# Punto2.net
KiCad netlist of a schematic drawn in Altium Designer
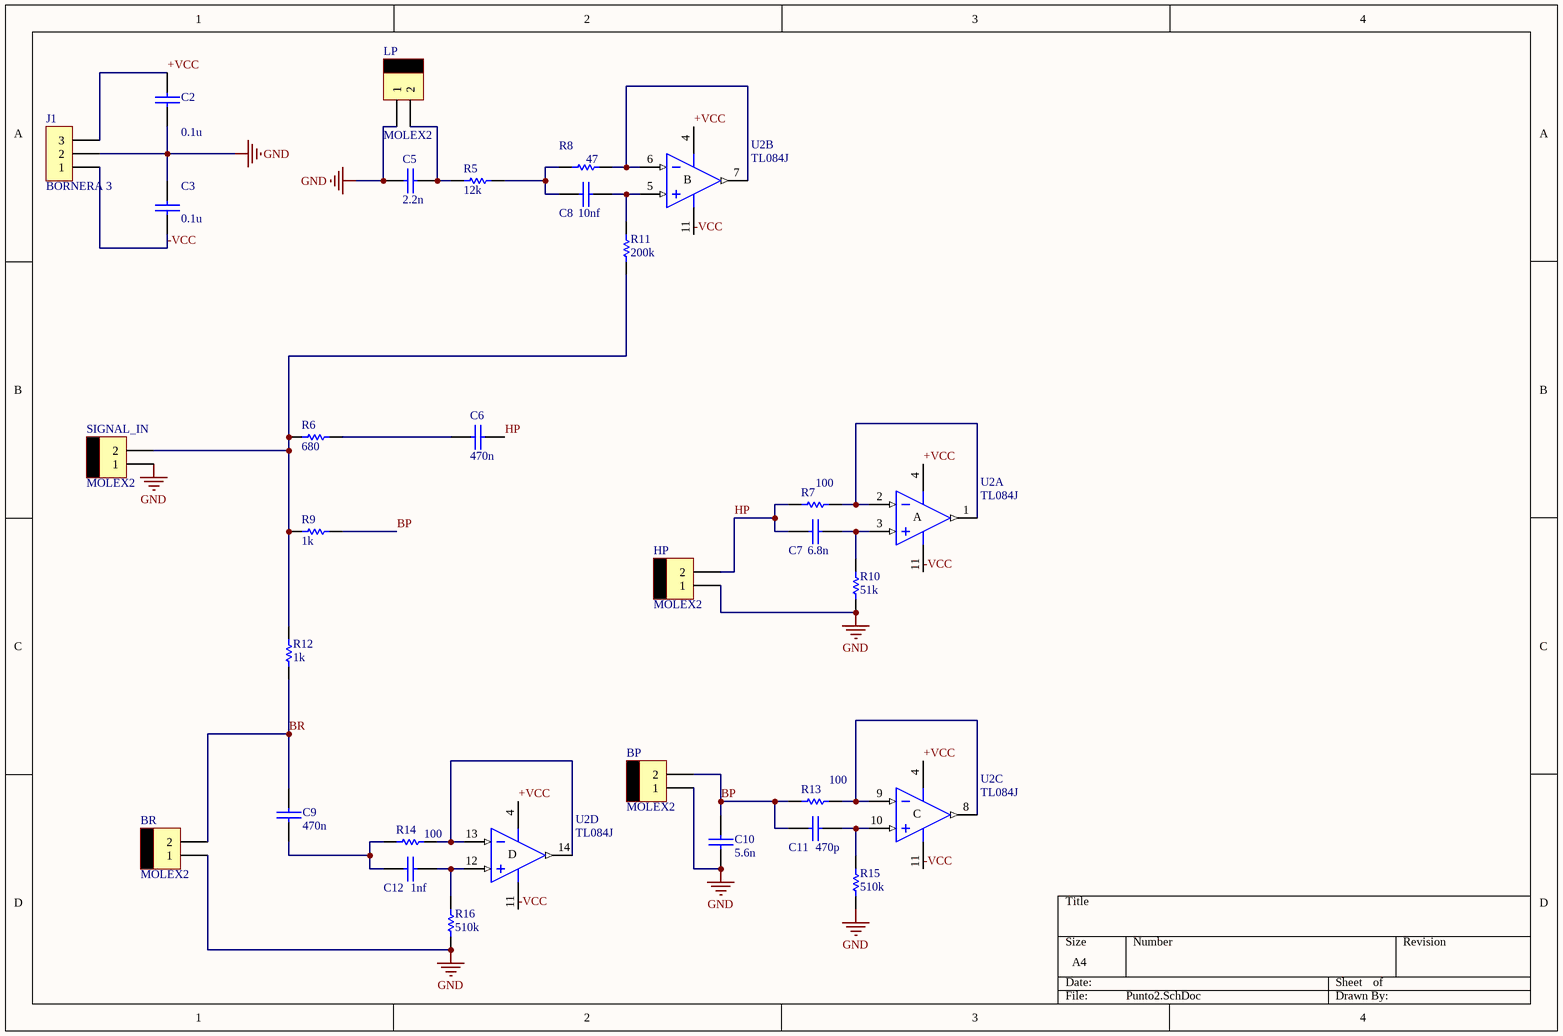
[diagram p0: Punto2.SchDoc]

(export (version "E")
  (design (tool "Eeschema 10.0.6"))
  (components
    (comp (ref "BP") (value "MOLEX2") (footprint "MOLEX2") (libsource (lib "LIBEBAL") (part "MOLEX2")))
    (comp (ref "BR") (value "MOLEX2") (footprint "MOLEX2") (libsource (lib "LIBEBAL") (part "MOLEX2")))
    (comp (ref "C2") (value "0.1u") (footprint "CAP200") (libsource (lib "LIBEBAL") (part "CAP")))
    (comp (ref "C3") (value "0.1u") (footprint "CAP200") (libsource (lib "LIBEBAL") (part "CAP")))
    (comp (ref "C5") (value "2.2n") (footprint "0805") (libsource (lib "LIBEBAL") (part "CAP")))
    (comp (ref "C6") (value "470n") (footprint "0805") (libsource (lib "LIBEBAL") (part "CAP")))
    (comp (ref "C7") (value "6.8n") (footprint "0805") (libsource (lib "LIBEBAL") (part "CAP")))
    (comp (ref "C8") (value "10nf") (footprint "0805") (libsource (lib "LIBEBAL") (part "CAP")))
    (comp (ref "C9") (value "470n") (footprint "0805") (libsource (lib "LIBEBAL") (part "CAP")))
    (comp (ref "C10") (value "5.6n") (footprint "0805") (libsource (lib "LIBEBAL") (part "CAP")))
    (comp (ref "C11") (value "470p") (footprint "0805") (libsource (lib "LIBEBAL") (part "CAP")))
    (comp (ref "C12") (value "1nf") (footprint "0805") (libsource (lib "LIBEBAL") (part "CAP")))
    (comp (ref "HP") (value "MOLEX2") (footprint "MOLEX2") (libsource (lib "LIBEBAL") (part "MOLEX2")))
    (comp (ref "J1")
      (value "BORNERA 3")
      (footprint "BORNERA3")
      (libsource (lib "LIBEBAL") (part "BORNERA 3"))
    )
    (comp (ref "LP") (value "MOLEX2") (footprint "MOLEX2") (libsource (lib "") (part "MOLEX2_1")))
    (comp (ref "R5") (value "12k") (footprint "0805") (libsource (lib "LIBEBAL") (part "RES")))
    (comp (ref "R6") (value "680") (footprint "0805") (libsource (lib "LIBEBAL") (part "RES")))
    (comp (ref "R7") (value "100") (footprint "0805") (libsource (lib "LIBEBAL") (part "RES")))
    (comp (ref "R8") (value "47") (footprint "0805") (libsource (lib "LIBEBAL") (part "RES")))
    (comp (ref "R9") (value "1k") (footprint "0805") (libsource (lib "LIBEBAL") (part "RES")))
    (comp (ref "R10") (value "51k") (footprint "0805") (libsource (lib "LIBEBAL") (part "RES")))
    (comp (ref "R11") (value "200k") (footprint "0805") (libsource (lib "LIBEBAL") (part "RES")))
    (comp (ref "R12") (value "1k") (footprint "0805") (libsource (lib "LIBEBAL") (part "RES")))
    (comp (ref "R13") (value "100") (footprint "0805") (libsource (lib "LIBEBAL") (part "RES")))
    (comp (ref "R14") (value "100") (footprint "0805") (libsource (lib "LIBEBAL") (part "RES")))
    (comp (ref "R15") (value "510k") (footprint "0805") (libsource (lib "LIBEBAL") (part "RES")))
    (comp (ref "R16") (value "510k") (footprint "0805") (libsource (lib "LIBEBAL") (part "RES")))
    (comp (ref "SIGNAL_IN") (value "MOLEX2") (footprint "MOLEX2") (libsource (lib "LIBEBAL") (part "MOLEX2")))
    (comp (ref "U2")
      (value "TL084J")
      (footprint "J014")
      (description "JFET-Input Operational Amplifier")
      (fields (field (name "PUBLISHER") "Altium Limited"))
      (libsource (lib "TI Operational Amplifier") (part "TL084J"))
    )
  )
  (nets
    (net (code "1") (name "/+VCC") (class "Default")
      (node (ref "C2") (pin "1") (pinfunction "1_1") (pintype "passive"))
      (node (ref "J1") (pin "3") (pinfunction "3_3") (pintype "passive"))
      (node (ref "U2") (pin "4") (pinfunction "V+_4") (pintype "power_in"))
    )
    (net (code "2") (name "/-VCC") (class "Default")
      (node (ref "C3") (pin "2") (pinfunction "2_2") (pintype "passive"))
      (node (ref "J1") (pin "1") (pinfunction "1_1") (pintype "passive"))
      (node (ref "U2") (pin "11") (pinfunction "V-_11") (pintype "power_in"))
    )
    (net (code "3") (name "/BP") (class "Default")
      (node (ref "BP") (pin "2") (pinfunction "2_2") (pintype "passive"))
      (node (ref "C10") (pin "1") (pinfunction "1_1") (pintype "passive"))
      (node (ref "C11") (pin "1") (pinfunction "1_1") (pintype "passive"))
      (node (ref "R13") (pin "1") (pinfunction "1_1") (pintype "passive"))
      (node (ref "R9") (pin "2") (pinfunction "2_2") (pintype "passive"))
    )
    (net (code "4") (name "/BR") (class "Default")
      (node (ref "BR") (pin "2") (pinfunction "2_2") (pintype "passive"))
      (node (ref "C9") (pin "2") (pinfunction "2_2") (pintype "passive"))
      (node (ref "R12") (pin "2") (pinfunction "2_2") (pintype "passive"))
    )
    (net (code "5") (name "/HP") (class "Default")
      (node (ref "C6") (pin "2") (pinfunction "2_2") (pintype "passive"))
      (node (ref "C7") (pin "1") (pinfunction "1_1") (pintype "passive"))
      (node (ref "HP") (pin "2") (pinfunction "2_2") (pintype "passive"))
      (node (ref "R7") (pin "1") (pinfunction "1_1") (pintype "passive"))
    )
    (net (code "6") (name "GND") (class "Default")
      (node (ref "BP") (pin "1") (pinfunction "1_1") (pintype "passive"))
      (node (ref "BR") (pin "1") (pinfunction "1_1") (pintype "passive"))
      (node (ref "C10") (pin "2") (pinfunction "2_2") (pintype "passive"))
      (node (ref "C2") (pin "2") (pinfunction "2_2") (pintype "passive"))
      (node (ref "C3") (pin "1") (pinfunction "1_1") (pintype "passive"))
      (node (ref "C5") (pin "2") (pinfunction "2_2") (pintype "passive"))
      (node (ref "HP") (pin "1") (pinfunction "1_1") (pintype "passive"))
      (node (ref "J1") (pin "2") (pinfunction "2_2") (pintype "passive"))
      (node (ref "LP") (pin "1") (pinfunction "1_1") (pintype "passive"))
      (node (ref "R10") (pin "1") (pinfunction "1_1") (pintype "passive"))
      (node (ref "R15") (pin "1") (pinfunction "1_1") (pintype "passive"))
      (node (ref "R16") (pin "1") (pinfunction "1_1") (pintype "passive"))
      (node (ref "SIGNAL_IN") (pin "1") (pinfunction "1_1") (pintype "passive"))
    )
    (net (code "7") (name "Net-(C5-Pad1)") (class "Default")
      (node (ref "C5") (pin "1") (pinfunction "1_1") (pintype "passive"))
      (node (ref "LP") (pin "2") (pinfunction "2_2") (pintype "passive"))
      (node (ref "R5") (pin "1") (pinfunction "1_1") (pintype "passive"))
    )
    (net (code "8") (name "Net-(C6-Pad1)") (class "Default")
      (node (ref "C6") (pin "1") (pinfunction "1_1") (pintype "passive"))
      (node (ref "R6") (pin "2") (pinfunction "2_2") (pintype "passive"))
    )
    (net (code "9") (name "Net-(C8-Pad1)") (class "Default")
      (node (ref "C8") (pin "1") (pinfunction "1_1") (pintype "passive"))
      (node (ref "R5") (pin "2") (pinfunction "2_2") (pintype "passive"))
      (node (ref "R8") (pin "1") (pinfunction "1_1") (pintype "passive"))
    )
    (net (code "10") (name "Net-(C12-Pad1)") (class "Default")
      (node (ref "C12") (pin "1") (pinfunction "1_1") (pintype "passive"))
      (node (ref "C9") (pin "1") (pinfunction "1_1") (pintype "passive"))
      (node (ref "R14") (pin "1") (pinfunction "1_1") (pintype "passive"))
    )
    (net (code "11") (name "Net-(R11-Pad1)") (class "Default")
      (node (ref "R11") (pin "1") (pinfunction "1_1") (pintype "passive"))
      (node (ref "R12") (pin "1") (pinfunction "1_1") (pintype "passive"))
      (node (ref "R6") (pin "1") (pinfunction "1_1") (pintype "passive"))
      (node (ref "R9") (pin "1") (pinfunction "1_1") (pintype "passive"))
      (node (ref "SIGNAL_IN") (pin "2") (pinfunction "2_2") (pintype "passive"))
    )
    (net (code "12") (name "Net-(U2A-IN+)") (class "Default")
      (node (ref "C7") (pin "2") (pinfunction "2_2") (pintype "passive"))
      (node (ref "R10") (pin "2") (pinfunction "2_2") (pintype "passive"))
      (node (ref "U2") (pin "3") (pinfunction "IN+_3") (pintype "input"))
    )
    (net (code "13") (name "Net-(U2A-IN-)") (class "Default")
      (node (ref "R7") (pin "2") (pinfunction "2_2") (pintype "passive"))
      (node (ref "U2") (pin "1") (pinfunction "OUT_1") (pintype "output"))
      (node (ref "U2") (pin "2") (pinfunction "IN-_2") (pintype "input"))
    )
    (net (code "14") (name "Net-(U2B-IN+)") (class "Default")
      (node (ref "C8") (pin "2") (pinfunction "2_2") (pintype "passive"))
      (node (ref "R11") (pin "2") (pinfunction "2_2") (pintype "passive"))
      (node (ref "U2") (pin "5") (pinfunction "IN+_5") (pintype "input"))
    )
    (net (code "15") (name "Net-(U2B-IN-)") (class "Default")
      (node (ref "R8") (pin "2") (pinfunction "2_2") (pintype "passive"))
      (node (ref "U2") (pin "6") (pinfunction "IN-_6") (pintype "input"))
      (node (ref "U2") (pin "7") (pinfunction "OUT_7") (pintype "output"))
    )
    (net (code "16") (name "Net-(U2C-IN+)") (class "Default")
      (node (ref "C11") (pin "2") (pinfunction "2_2") (pintype "passive"))
      (node (ref "R15") (pin "2") (pinfunction "2_2") (pintype "passive"))
      (node (ref "U2") (pin "10") (pinfunction "IN+_10") (pintype "input"))
    )
    (net (code "17") (name "Net-(U2C-IN-)") (class "Default")
      (node (ref "R13") (pin "2") (pinfunction "2_2") (pintype "passive"))
      (node (ref "U2") (pin "8") (pinfunction "OUT_8") (pintype "output"))
      (node (ref "U2") (pin "9") (pinfunction "IN-_9") (pintype "input"))
    )
    (net (code "18") (name "Net-(U2D-IN+)") (class "Default")
      (node (ref "C12") (pin "2") (pinfunction "2_2") (pintype "passive"))
      (node (ref "R16") (pin "2") (pinfunction "2_2") (pintype "passive"))
      (node (ref "U2") (pin "12") (pinfunction "IN+_12") (pintype "input"))
    )
    (net (code "19") (name "Net-(U2D-IN-)") (class "Default")
      (node (ref "R14") (pin "2") (pinfunction "2_2") (pintype "passive"))
      (node (ref "U2") (pin "13") (pinfunction "IN-_13") (pintype "input"))
      (node (ref "U2") (pin "14") (pinfunction "OUT_14") (pintype "output"))
    )
  )
)
